# STM8_FootPrint.net
KiCad netlist of a schematic drawn in Altium Designer
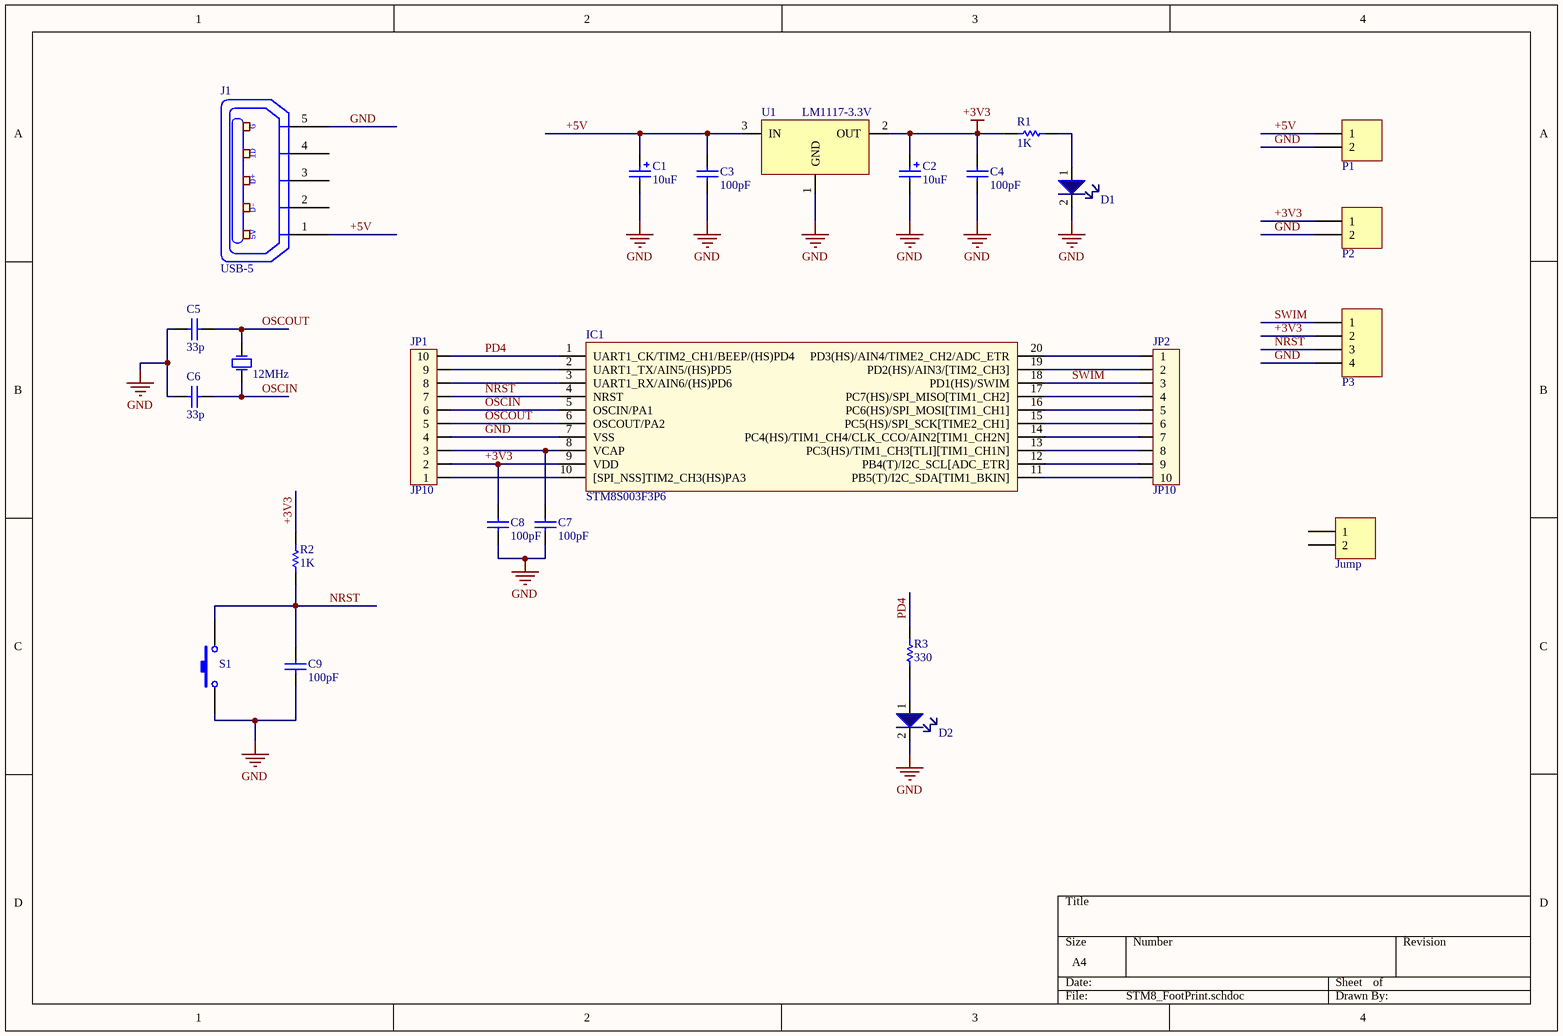
[diagram p0: STM8_FootPrint.schdoc]

(export (version "E")
  (design (tool "Eeschema 10.0.6"))
  (components
    (comp (ref "C1")
      (value "10uF")
      (footprint "CP1/2")
      (description "Polarized Capacitor (Radial)")
      (fields (field (name "Comment") "Cap Pol"))
      (libsource (lib "PIF_Library") (part "Cap Pol"))
    )
    (comp (ref "C2")
      (value "10uF")
      (footprint "CP1/2")
      (description "Polarized Capacitor (Radial)")
      (fields (field (name "Comment") "Cap Pol"))
      (libsource (lib "PIF_Library") (part "Cap Pol"))
    )
    (comp (ref "C3")
      (value "100pF")
      (footprint "CAP-SM-0805")
      (description "Capacitor")
      (fields (field (name "Comment") "Cap Non-Pol SMD"))
      (libsource (lib "PIF_Library") (part "Cap Non-Pol SMD"))
    )
    (comp (ref "C4")
      (value "100pF")
      (footprint "CAP-SM-0805")
      (description "Capacitor")
      (fields (field (name "Comment") "Cap Non-Pol SMD"))
      (libsource (lib "PIF_Library") (part "Cap Non-Pol SMD"))
    )
    (comp (ref "C5")
      (value "33p")
      (footprint "Tu-ceramic")
      (description "Capacitor")
      (fields (field (name "Comment") "Capacitor Ceramic") (field (name "PUBLISHER") "Altium Limited"))
      (libsource (lib "NBBLib 14-03-2012") (part "CapDecop"))
    )
    (comp (ref "C6")
      (value "33p")
      (footprint "Tu-ceramic")
      (description "Capacitor")
      (fields (field (name "Comment") "Capacitor Ceramic") (field (name "PUBLISHER") "Altium Limited"))
      (libsource (lib "NBBLib 14-03-2012") (part "CapDecop"))
    )
    (comp (ref "C7")
      (value "100pF")
      (footprint "CAP-SM-0805")
      (description "Capacitor")
      (fields (field (name "Comment") "Cap Non-Pol SMD"))
      (libsource (lib "PIF_Library") (part "Cap Non-Pol SMD"))
    )
    (comp (ref "C8")
      (value "100pF")
      (footprint "CAP-SM-0805")
      (description "Capacitor")
      (fields (field (name "Comment") "Cap Non-Pol SMD"))
      (libsource (lib "PIF_Library") (part "Cap Non-Pol SMD"))
    )
    (comp (ref "C9")
      (value "100pF")
      (footprint "CAP-SM-0805")
      (description "Capacitor")
      (fields (field (name "Comment") "Cap Non-Pol SMD"))
      (libsource (lib "PIF_Library") (part "Cap Non-Pol SMD"))
    )
    (comp (ref "D1") (value "LED") (footprint "LED 3mm") (libsource (lib "C15") (part "LED")))
    (comp (ref "D2") (value "LED") (footprint "LED 3mm") (libsource (lib "C15") (part "LED")))
    (comp (ref "IC1")
      (value "STM8S003F3P6")
      (footprint "TSSOP20")
      (description "MCU 8BIT  8KB FLASH TSSOP-20")
      (fields (field (name "COPYRIGHT BY") "VanDungEvn"))
      (libsource (lib "LIBRARY") (part "STM8S003F3P6"))
    )
    (comp (ref "J1")
      (value "USB-5")
      (footprint "USB-M2")
      (fields
        (field (name "MANUFACTURER") "FCI")
        (field (name "MANUFACTURER PART NUMBER") "10118193-0001LF")
        (field (name ".CREATOR") "MM")
        (field (name ".CHECKED PCB") "RF")
        (field (name ".CHECKED SCH") "MM")
      )
      (libsource (lib "LIBRARY") (part "USB-5"))
    )
    (comp (ref "JP1")
      (value "JP10")
      (footprint "Header10")
      (description "Connector 10")
      (libsource (lib "") (part "Header10_1"))
    )
    (comp (ref "JP2")
      (value "JP10")
      (footprint "Header10")
      (description "Connector 10")
      (libsource (lib "LIBRARY") (part "Header10"))
    )
    (comp (ref "Jump")
      (value "Header 2")
      (footprint "JP2")
      (description "Header, 2-Pin")
      (fields (field (name "PUBLISHER") "Altium Limited"))
      (libsource (lib "PIF_Library") (part "Header 2"))
    )
    (comp (ref "P1")
      (value "Header 2")
      (footprint "JP2")
      (description "Header, 2-Pin")
      (fields (field (name "PUBLISHER") "Altium Limited"))
      (libsource (lib "PIF_Library") (part "Header 2"))
    )
    (comp (ref "P2")
      (value "Header 2")
      (footprint "JP2")
      (description "Header, 2-Pin")
      (fields (field (name "PUBLISHER") "Altium Limited"))
      (libsource (lib "PIF_Library") (part "Header 2"))
    )
    (comp (ref "P3")
      (value "Header 4")
      (footprint "JP4")
      (description "Header, 4-Pin")
      (fields (field (name "PUBLISHER") "Altium Limited"))
      (libsource (lib "PIF_Library") (part "Header 4"))
    )
    (comp (ref "R1")
      (value "1K")
      (footprint "RES-SM-0805")
      (description "Resistor")
      (fields (field (name "Comment") "RESISTOR SMD"))
      (libsource (lib "PIF_Library") (part "RESISTOR SMD"))
    )
    (comp (ref "R2")
      (value "1K")
      (footprint "RES-SM-0805")
      (description "Resistor")
      (fields (field (name "Comment") "RESISTOR SMD"))
      (libsource (lib "PIF_Library") (part "RESISTOR SMD"))
    )
    (comp (ref "R3")
      (value "330")
      (footprint "RES-SM-0805")
      (description "Resistor")
      (fields (field (name "Comment") "RESISTOR SMD"))
      (libsource (lib "PIF_Library") (part "RESISTOR SMD"))
    )
    (comp (ref "S1")
      (value "Tact SW - 2Pin")
      (footprint "SW2")
      (description "Switch button 2 pin")
      (libsource (lib "PIF_Library") (part "Tact SW - 2Pin"))
    )
    (comp (ref "U1")
      (value "LM1117-3.3V")
      (footprint "SOT223")
      (description "800mA Low-Dropout Linear Regulator")
      (fields (field (name "CREATOR") "Nguyen Ba Bien"))
      (libsource (lib "LIBRARY") (part "LM1117"))
    )
    (comp (ref "Y1")
      (value "12MHz")
      (footprint "XTAL")
      (description "Crystal Oscillator")
      (fields (field (name "PUBLISHER") "Altium Limited"))
      (libsource (lib "NBBLib 14-03-2012") (part "XTAL"))
    )
  )
  (nets
    (net (code "1") (name "+3V3") (class "Default")
      (node (ref "C2") (pin "1") (pinfunction "1_1") (pintype "passive"))
      (node (ref "C4") (pin "1") (pinfunction "1_1") (pintype "passive"))
      (node (ref "C8") (pin "1") (pinfunction "1_1") (pintype "passive"))
      (node (ref "IC1") (pin "9") (pinfunction "VDD_9") (pintype "passive"))
      (node (ref "JP1") (pin "2") (pinfunction "2_2") (pintype "passive"))
      (node (ref "P2") (pin "1") (pinfunction "1_1") (pintype "passive"))
      (node (ref "P3") (pin "2") (pinfunction "2_2") (pintype "passive"))
      (node (ref "R1") (pin "1") (pinfunction "1_1") (pintype "passive"))
      (node (ref "R2") (pin "2") (pinfunction "2_2") (pintype "passive"))
      (node (ref "U1") (pin "2") (pinfunction "OUT_2") (pintype "passive"))
    )
    (net (code "2") (name "/+5V") (class "Default")
      (node (ref "C1") (pin "1") (pinfunction "1_1") (pintype "passive"))
      (node (ref "C3") (pin "1") (pinfunction "1_1") (pintype "passive"))
      (node (ref "J1") (pin "1") (pinfunction "P1_1") (pintype "passive"))
      (node (ref "P1") (pin "1") (pinfunction "1_1") (pintype "passive"))
      (node (ref "U1") (pin "3") (pinfunction "IN_3") (pintype "passive"))
    )
    (net (code "3") (name "/NRST") (class "Default")
      (node (ref "C9") (pin "1") (pinfunction "1_1") (pintype "passive"))
      (node (ref "IC1") (pin "4") (pinfunction "NRST_4") (pintype "passive"))
      (node (ref "JP1") (pin "7") (pinfunction "7_7") (pintype "passive"))
      (node (ref "P3") (pin "3") (pinfunction "3_3") (pintype "passive"))
      (node (ref "R2") (pin "1") (pinfunction "1_1") (pintype "passive"))
      (node (ref "S1") (pin "2") (pinfunction "2_2") (pintype "passive"))
    )
    (net (code "4") (name "/OSCIN") (class "Default")
      (node (ref "C6") (pin "2") (pinfunction "2_2") (pintype "passive"))
      (node (ref "IC1") (pin "5") (pinfunction "OSCIN/PA1_5") (pintype "passive"))
      (node (ref "JP1") (pin "6") (pinfunction "6_6") (pintype "passive"))
      (node (ref "Y1") (pin "2") (pinfunction "OSC2_2") (pintype "passive"))
    )
    (net (code "5") (name "/OSCOUT") (class "Default")
      (node (ref "C5") (pin "2") (pinfunction "2_2") (pintype "passive"))
      (node (ref "IC1") (pin "6") (pinfunction "OSCOUT/PA2_6") (pintype "passive"))
      (node (ref "JP1") (pin "5") (pinfunction "5_5") (pintype "passive"))
      (node (ref "Y1") (pin "1") (pinfunction "OSC1_1") (pintype "passive"))
    )
    (net (code "6") (name "/PD4") (class "Default")
      (node (ref "IC1") (pin "1") (pinfunction "UART1_CK/TIM2_CH1/BEEP/(HS)PD4_1") (pintype "passive"))
      (node (ref "JP1") (pin "10") (pinfunction "10_10") (pintype "passive"))
      (node (ref "R3") (pin "2") (pinfunction "2_2") (pintype "passive"))
    )
    (net (code "7") (name "/SWIM") (class "Default")
      (node (ref "IC1") (pin "18") (pinfunction "PD1(HS)/SWIM_18") (pintype "passive"))
      (node (ref "JP2") (pin "3") (pinfunction "3_3") (pintype "passive"))
      (node (ref "P3") (pin "1") (pinfunction "1_1") (pintype "passive"))
    )
    (net (code "8") (name "GND") (class "Default")
      (node (ref "C1") (pin "2") (pinfunction "2_2") (pintype "passive"))
      (node (ref "C2") (pin "2") (pinfunction "2_2") (pintype "passive"))
      (node (ref "C3") (pin "2") (pinfunction "2_2") (pintype "passive"))
      (node (ref "C4") (pin "2") (pinfunction "2_2") (pintype "passive"))
      (node (ref "C5") (pin "1") (pinfunction "1_1") (pintype "passive"))
      (node (ref "C6") (pin "1") (pinfunction "1_1") (pintype "passive"))
      (node (ref "C7") (pin "2") (pinfunction "2_2") (pintype "passive"))
      (node (ref "C8") (pin "2") (pinfunction "2_2") (pintype "passive"))
      (node (ref "C9") (pin "2") (pinfunction "2_2") (pintype "passive"))
      (node (ref "D1") (pin "2") (pintype "passive"))
      (node (ref "D2") (pin "2") (pintype "passive"))
      (node (ref "IC1") (pin "7") (pinfunction "VSS_7") (pintype "passive"))
      (node (ref "J1") (pin "5") (pinfunction "P5_5") (pintype "passive"))
      (node (ref "JP1") (pin "4") (pinfunction "4_4") (pintype "passive"))
      (node (ref "P1") (pin "2") (pinfunction "2_2") (pintype "passive"))
      (node (ref "P2") (pin "2") (pinfunction "2_2") (pintype "passive"))
      (node (ref "P3") (pin "4") (pinfunction "4_4") (pintype "passive"))
      (node (ref "S1") (pin "1") (pinfunction "1_1") (pintype "passive"))
      (node (ref "U1") (pin "1") (pinfunction "GND_1") (pintype "passive"))
    )
    (net (code "9") (name "Net-(D1-Pad1)") (class "Default")
      (node (ref "D1") (pin "1") (pintype "passive"))
      (node (ref "R1") (pin "2") (pinfunction "2_2") (pintype "passive"))
    )
    (net (code "10") (name "Net-(D2-Pad1)") (class "Default")
      (node (ref "D2") (pin "1") (pintype "passive"))
      (node (ref "R3") (pin "1") (pinfunction "1_1") (pintype "passive"))
    )
    (net (code "11") (name "Net-(IC1-PB4(T){slash}I2C_SCL[ADC_ETR])") (class "Default")
      (node (ref "IC1") (pin "12") (pinfunction "PB4(T)/I2C_SCL[ADC_ETR]_12") (pintype "passive"))
      (node (ref "JP2") (pin "9") (pinfunction "9_9") (pintype "passive"))
    )
    (net (code "12") (name "Net-(IC1-PB5(T){slash}I2C_SDA[TIM1_BKIN])") (class "Default")
      (node (ref "IC1") (pin "11") (pinfunction "PB5(T)/I2C_SDA[TIM1_BKIN]_11") (pintype "passive"))
      (node (ref "JP2") (pin "10") (pinfunction "10_10") (pintype "passive"))
    )
    (net (code "13") (name "Net-(IC1-PC3(HS){slash}TIM1_CH3[TLI][TIM1_CH1N])") (class "Default")
      (node (ref "IC1") (pin "13") (pinfunction "PC3(HS)/TIM1_CH3[TLI][TIM1_CH1N]_13") (pintype "passive"))
      (node (ref "JP2") (pin "8") (pinfunction "8_8") (pintype "passive"))
    )
    (net (code "14") (name "Net-(IC1-PC4(HS){slash}TIM1_CH4{slash}CLK_CCO{slash}AIN2[TIM1_CH2N])") (class "Default")
      (node (ref "IC1") (pin "14") (pinfunction "PC4(HS)/TIM1_CH4/CLK_CCO/AIN2[TIM1_CH2N]_14") (pintype "passive"))
      (node (ref "JP2") (pin "7") (pinfunction "7_7") (pintype "passive"))
    )
    (net (code "15") (name "Net-(IC1-PC5(HS){slash}SPI_SCK[TIME2_CH1])") (class "Default")
      (node (ref "IC1") (pin "15") (pinfunction "PC5(HS)/SPI_SCK[TIME2_CH1]_15") (pintype "passive"))
      (node (ref "JP2") (pin "6") (pinfunction "6_6") (pintype "passive"))
    )
    (net (code "16") (name "Net-(IC1-PC6(HS){slash}SPI_MOSI[TIM1_CH1])") (class "Default")
      (node (ref "IC1") (pin "16") (pinfunction "PC6(HS)/SPI_MOSI[TIM1_CH1]_16") (pintype "passive"))
      (node (ref "JP2") (pin "5") (pinfunction "5_5") (pintype "passive"))
    )
    (net (code "17") (name "Net-(IC1-PC7(HS){slash}SPI_MISO[TIM1_CH2])") (class "Default")
      (node (ref "IC1") (pin "17") (pinfunction "PC7(HS)/SPI_MISO[TIM1_CH2]_17") (pintype "passive"))
      (node (ref "JP2") (pin "4") (pinfunction "4_4") (pintype "passive"))
    )
    (net (code "18") (name "Net-(IC1-PD2(HS){slash}AIN3{slash}[TIM2_CH3])") (class "Default")
      (node (ref "IC1") (pin "19") (pinfunction "PD2(HS)/AIN3/[TIM2_CH3]_19") (pintype "passive"))
      (node (ref "JP2") (pin "2") (pinfunction "2_2") (pintype "passive"))
    )
    (net (code "19") (name "Net-(IC1-PD3(HS){slash}AIN4{slash}TIME2_CH2{slash}ADC_ETR)") (class "Default")
      (node (ref "IC1") (pin "20") (pinfunction "PD3(HS)/AIN4/TIME2_CH2/ADC_ETR_20") (pintype "passive"))
      (node (ref "JP2") (pin "1") (pinfunction "1_1") (pintype "passive"))
    )
    (net (code "20") (name "Net-(IC1-UART1_RX{slash}AIN6{slash}(HS)PD6)") (class "Default")
      (node (ref "IC1") (pin "3") (pinfunction "UART1_RX/AIN6/(HS)PD6_3") (pintype "passive"))
      (node (ref "JP1") (pin "8") (pinfunction "8_8") (pintype "passive"))
    )
    (net (code "21") (name "Net-(IC1-UART1_TX{slash}AIN5{slash}(HS)PD5)") (class "Default")
      (node (ref "IC1") (pin "2") (pinfunction "UART1_TX/AIN5/(HS)PD5_2") (pintype "passive"))
      (node (ref "JP1") (pin "9") (pinfunction "9_9") (pintype "passive"))
    )
    (net (code "22") (name "Net-(IC1-VCAP)") (class "Default")
      (node (ref "C7") (pin "1") (pinfunction "1_1") (pintype "passive"))
      (node (ref "IC1") (pin "8") (pinfunction "VCAP_8") (pintype "passive"))
      (node (ref "JP1") (pin "3") (pinfunction "3_3") (pintype "passive"))
    )
    (net (code "23") (name "Net-(IC1-[SPI_NSS]TIM2_CH3(HS)PA3)") (class "Default")
      (node (ref "IC1") (pin "10") (pinfunction "[SPI_NSS]TIM2_CH3(HS)PA3_10") (pintype "passive"))
      (node (ref "JP1") (pin "1") (pinfunction "1_1") (pintype "passive"))
    )
    (net (code "24") (name "unconnected-(J1-P2-Pad2)") (class "Default")
      (node (ref "J1") (pin "2") (pinfunction "P2_2") (pintype "passive"))
    )
    (net (code "25") (name "unconnected-(J1-P3-Pad3)") (class "Default")
      (node (ref "J1") (pin "3") (pinfunction "P3_3") (pintype "passive"))
    )
    (net (code "26") (name "unconnected-(J1-P4-Pad4)") (class "Default")
      (node (ref "J1") (pin "4") (pinfunction "P4_4") (pintype "passive"))
    )
    (net (code "27") (name "unconnected-(Jump-Pad1)") (class "Default")
      (node (ref "Jump") (pin "1") (pinfunction "1_1") (pintype "passive"))
    )
    (net (code "28") (name "unconnected-(Jump-Pad2)") (class "Default")
      (node (ref "Jump") (pin "2") (pinfunction "2_2") (pintype "passive"))
    )
  )
)
